# ECG_V1_1.net
KiCad netlist of a schematic drawn in EAGLE
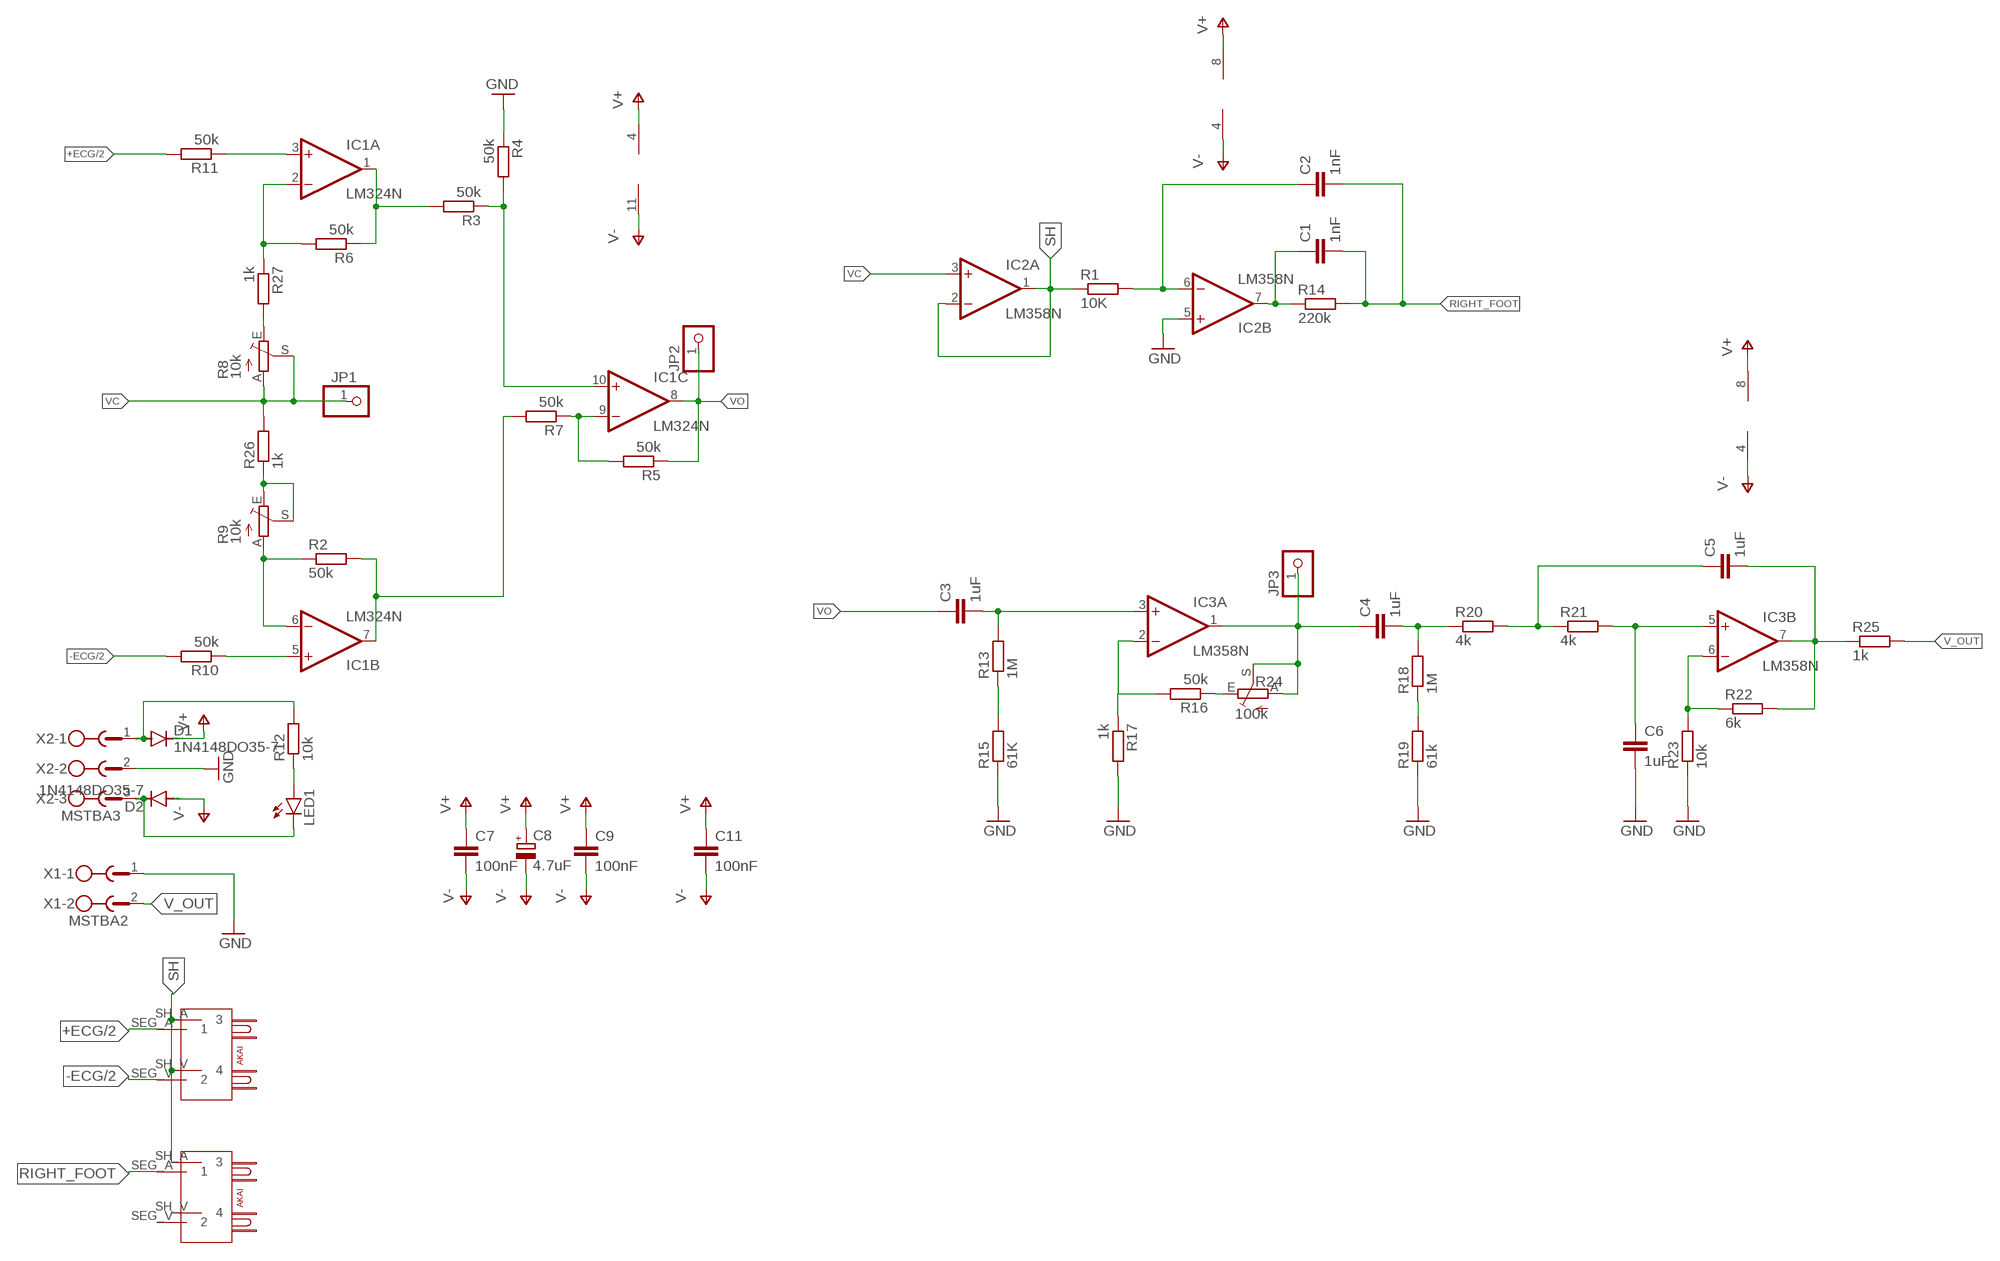
[diagram p0: schematic, sheet 1]

(export (version "E")
  (design (tool "Eeschema 10.0.6"))
  (components
    (comp (ref "C1")
      (value "1nF")
      (footprint "eagle-import:C050-024X044")
      (libsource (lib "eagle-import") (part "C-EU050-024X044"))
    )
    (comp (ref "C2")
      (value "1nF")
      (footprint "eagle-import:C050-024X044")
      (libsource (lib "eagle-import") (part "C-EU050-024X044"))
    )
    (comp (ref "C3")
      (value "1uF")
      (footprint "eagle-import:C075-032X103")
      (libsource (lib "eagle-import") (part "C-EU075-032X103"))
    )
    (comp (ref "C4")
      (value "1uF")
      (footprint "eagle-import:C050-024X044")
      (libsource (lib "eagle-import") (part "C-EU050-024X044"))
    )
    (comp (ref "C5")
      (value "1uF")
      (footprint "eagle-import:C050-024X044")
      (libsource (lib "eagle-import") (part "C-EU050-024X044"))
    )
    (comp (ref "C6")
      (value "1uF")
      (footprint "eagle-import:C050-024X044")
      (libsource (lib "eagle-import") (part "C-EU050-024X044"))
    )
    (comp (ref "C7")
      (value "100nF")
      (footprint "eagle-import:C050-024X044")
      (libsource (lib "eagle-import") (part "C-EU050-024X044"))
    )
    (comp (ref "C8")
      (value "4.7uF")
      (footprint "eagle-import:E2-4")
      (libsource (lib "eagle-import") (part "CPOL-EUE2-4"))
    )
    (comp (ref "C9")
      (value "100nF")
      (footprint "eagle-import:C050-024X044")
      (libsource (lib "eagle-import") (part "C-EU050-024X044"))
    )
    (comp (ref "C11")
      (value "100nF")
      (footprint "eagle-import:C050-024X044")
      (libsource (lib "eagle-import") (part "C-EU050-024X044"))
    )
    (comp (ref "D1")
      (value "1N4148DO35-7")
      (footprint "eagle-import:DO35-7")
      (libsource (lib "eagle-import") (part "1N4148DO35-7"))
    )
    (comp (ref "D2")
      (value "1N4148DO35-7")
      (footprint "eagle-import:DO35-7")
      (libsource (lib "eagle-import") (part "1N4148DO35-7"))
    )
    (comp (ref "IC1")
      (value "LM324N")
      (footprint "eagle-import:DIL14")
      (libsource (lib "eagle-import") (part "LM324N"))
    )
    (comp (ref "IC2")
      (value "LM358N")
      (footprint "eagle-import:DIL08")
      (libsource (lib "eagle-import") (part "LM358N"))
    )
    (comp (ref "IC3")
      (value "LM358N")
      (footprint "eagle-import:DIL08")
      (libsource (lib "eagle-import") (part "LM358N"))
    )
    (comp (ref "JP1")
      (value "PINHD-1X1")
      (footprint "eagle-import:1X01")
      (libsource (lib "eagle-import") (part "PINHD-1X1"))
    )
    (comp (ref "JP2")
      (value "PINHD-1X1")
      (footprint "eagle-import:1X01")
      (libsource (lib "eagle-import") (part "PINHD-1X1"))
    )
    (comp (ref "JP3")
      (value "PINHD-1X1")
      (footprint "eagle-import:1X01")
      (libsource (lib "eagle-import") (part "PINHD-1X1"))
    )
    (comp (ref "LED1")
      (value "LED3MM")
      (footprint "eagle-import:LED3MM")
      (libsource (lib "eagle-import") (part "LED3MM"))
    )
    (comp (ref "R1")
      (value "10K")
      (footprint "eagle-import:0207_7")
      (libsource (lib "eagle-import") (part "R-EU_0207/7"))
    )
    (comp (ref "R2")
      (value "50k")
      (footprint "eagle-import:0207_7")
      (libsource (lib "eagle-import") (part "R-EU_0207/7"))
    )
    (comp (ref "R3")
      (value "50k")
      (footprint "eagle-import:0207_7")
      (libsource (lib "eagle-import") (part "R-EU_0207/7"))
    )
    (comp (ref "R4")
      (value "50k")
      (footprint "eagle-import:0207_7")
      (libsource (lib "eagle-import") (part "R-EU_0207/7"))
    )
    (comp (ref "R5")
      (value "50k")
      (footprint "eagle-import:0207_7")
      (libsource (lib "eagle-import") (part "R-EU_0207/7"))
    )
    (comp (ref "R6")
      (value "50k")
      (footprint "eagle-import:0207_7")
      (libsource (lib "eagle-import") (part "R-EU_0207/7"))
    )
    (comp (ref "R7")
      (value "50k")
      (footprint "eagle-import:0207_7")
      (libsource (lib "eagle-import") (part "R-EU_0207/7"))
    )
    (comp (ref "R8")
      (value "10k")
      (footprint "eagle-import:S64W")
      (libsource (lib "eagle-import") (part "TRIM_EU-S64W"))
    )
    (comp (ref "R9")
      (value "10k")
      (footprint "eagle-import:S64W")
      (libsource (lib "eagle-import") (part "TRIM_EU-S64W"))
    )
    (comp (ref "R10")
      (value "50k")
      (footprint "eagle-import:0207_7")
      (libsource (lib "eagle-import") (part "R-EU_0207/7"))
    )
    (comp (ref "R11")
      (value "50k")
      (footprint "eagle-import:0207_7")
      (libsource (lib "eagle-import") (part "R-EU_0207/7"))
    )
    (comp (ref "R12")
      (value "10k")
      (footprint "eagle-import:0207_7")
      (libsource (lib "eagle-import") (part "R-EU_0207/7"))
    )
    (comp (ref "R13")
      (value "1M")
      (footprint "eagle-import:0207_7")
      (libsource (lib "eagle-import") (part "R-EU_0207/7"))
    )
    (comp (ref "R14")
      (value "220k")
      (footprint "eagle-import:0207_7")
      (libsource (lib "eagle-import") (part "R-EU_0207/7"))
    )
    (comp (ref "R15")
      (value "61K")
      (footprint "eagle-import:0207_7")
      (libsource (lib "eagle-import") (part "R-EU_0207/7"))
    )
    (comp (ref "R16")
      (value "50k")
      (footprint "eagle-import:0207_7")
      (libsource (lib "eagle-import") (part "R-EU_0207/7"))
    )
    (comp (ref "R17")
      (value "1k")
      (footprint "eagle-import:0207_7")
      (libsource (lib "eagle-import") (part "R-EU_0207/7"))
    )
    (comp (ref "R18")
      (value "1M")
      (footprint "eagle-import:0207_7")
      (libsource (lib "eagle-import") (part "R-EU_0207/7"))
    )
    (comp (ref "R19")
      (value "61k")
      (footprint "eagle-import:0207_7")
      (libsource (lib "eagle-import") (part "R-EU_0207/7"))
    )
    (comp (ref "R20")
      (value "4k")
      (footprint "eagle-import:0207_7")
      (libsource (lib "eagle-import") (part "R-EU_0207/7"))
    )
    (comp (ref "R21")
      (value "4k")
      (footprint "eagle-import:0207_7")
      (libsource (lib "eagle-import") (part "R-EU_0207/7"))
    )
    (comp (ref "R22")
      (value "6k")
      (footprint "eagle-import:0207_7")
      (libsource (lib "eagle-import") (part "R-EU_0207/7"))
    )
    (comp (ref "R23")
      (value "10k")
      (footprint "eagle-import:0207_7")
      (libsource (lib "eagle-import") (part "R-EU_0207/7"))
    )
    (comp (ref "R24")
      (value "100k")
      (footprint "eagle-import:S64W")
      (libsource (lib "eagle-import") (part "TRIM_EU-S64W"))
    )
    (comp (ref "R25")
      (value "1k")
      (footprint "eagle-import:0207_7")
      (libsource (lib "eagle-import") (part "R-EU_0207/7"))
    )
    (comp (ref "R26")
      (value "1k")
      (footprint "eagle-import:0207_7")
      (libsource (lib "eagle-import") (part "R-EU_0207/7"))
    )
    (comp (ref "R27")
      (value "1k")
      (footprint "eagle-import:0207_7")
      (libsource (lib "eagle-import") (part "R-EU_0207/7"))
    )
    (comp (ref "U$1")
      (value "AKAI")
      (footprint "eagle-import:DUAL_AKAI")
      (libsource (lib "eagle-import") (part "AKAI"))
    )
    (comp (ref "U$2")
      (value "AKAI")
      (footprint "eagle-import:DUAL_AKAI")
      (libsource (lib "eagle-import") (part "AKAI"))
    )
    (comp (ref "X1")
      (value "MSTBA2")
      (footprint "eagle-import:MSTBA2")
      (fields (field (name "MF") "FARNELL") (field (name "MPN") "1757242"))
      (libsource (lib "eagle-import") (part "MSTBA2"))
    )
    (comp (ref "X2")
      (value "MSTBA3")
      (footprint "eagle-import:MSTBA3")
      (fields (field (name "MF") "FARNELL") (field (name "MPN") "1757255"))
      (libsource (lib "eagle-import") (part "MSTBA3"))
    )
  )
  (nets
    (net (code "1") (name "+ECG{slash}2") (class "Default")
      (node (ref "R11") (pin "2") (pinfunction "2_2") (pintype "passive"))
      (node (ref "U$1") (pin "SEG_A") (pinfunction "1_SEG_A") (pintype "bidirectional"))
    )
    (net (code "2") (name "-ECG{slash}2") (class "Default")
      (node (ref "R10") (pin "2") (pinfunction "2_2") (pintype "passive"))
      (node (ref "U$1") (pin "SEG_V") (pinfunction "2_SEG_V") (pintype "bidirectional"))
    )
    (net (code "3") (name "GND") (class "Default")
      (node (ref "C6") (pin "2") (pinfunction "2_2") (pintype "passive"))
      (node (ref "IC2") (pin "5") (pinfunction "+IN_5") (pintype "input"))
      (node (ref "R15") (pin "1") (pinfunction "1_1") (pintype "passive"))
      (node (ref "R17") (pin "2") (pinfunction "2_2") (pintype "passive"))
      (node (ref "R19") (pin "1") (pinfunction "1_1") (pintype "passive"))
      (node (ref "R23") (pin "1") (pinfunction "1_1") (pintype "passive"))
      (node (ref "R4") (pin "1") (pinfunction "1_1") (pintype "passive"))
      (node (ref "X1") (pin "1") (pinfunction "1_1") (pintype "passive"))
      (node (ref "X2") (pin "2") (pinfunction "1_2") (pintype "passive"))
    )
    (net (code "4") (name "Net-(C4-Pad2)") (class "Default")
      (node (ref "C4") (pin "2") (pinfunction "2_2") (pintype "passive"))
      (node (ref "R18") (pin "2") (pinfunction "2_2") (pintype "passive"))
      (node (ref "R20") (pin "1") (pinfunction "1_1") (pintype "passive"))
    )
    (net (code "5") (name "Net-(C5-Pad1)") (class "Default")
      (node (ref "C5") (pin "1") (pinfunction "1_1") (pintype "passive"))
      (node (ref "R20") (pin "2") (pinfunction "2_2") (pintype "passive"))
      (node (ref "R21") (pin "1") (pinfunction "1_1") (pintype "passive"))
    )
    (net (code "6") (name "Net-(D1-PadA)") (class "Default")
      (node (ref "D1") (pin "A") (pinfunction "A_A") (pintype "passive"))
      (node (ref "R12") (pin "2") (pinfunction "2_2") (pintype "passive"))
      (node (ref "X2") (pin "1") (pinfunction "1_1") (pintype "passive"))
    )
    (net (code "7") (name "Net-(IC1A-+IN)") (class "Default")
      (node (ref "IC1") (pin "3") (pinfunction "+IN_3") (pintype "input"))
      (node (ref "R11") (pin "1") (pinfunction "1_1") (pintype "passive"))
    )
    (net (code "8") (name "Net-(IC1A--IN)") (class "Default")
      (node (ref "IC1") (pin "2") (pinfunction "-IN_2") (pintype "input"))
      (node (ref "R27") (pin "1") (pinfunction "1_1") (pintype "passive"))
      (node (ref "R6") (pin "2") (pinfunction "2_2") (pintype "passive"))
    )
    (net (code "9") (name "Net-(IC1A-OUT)") (class "Default")
      (node (ref "IC1") (pin "1") (pinfunction "OUT_1") (pintype "output"))
      (node (ref "R3") (pin "2") (pinfunction "2_2") (pintype "passive"))
      (node (ref "R6") (pin "1") (pinfunction "1_1") (pintype "passive"))
    )
    (net (code "10") (name "Net-(IC1B-+IN)") (class "Default")
      (node (ref "IC1") (pin "5") (pinfunction "+IN_5") (pintype "input"))
      (node (ref "R10") (pin "1") (pinfunction "1_1") (pintype "passive"))
    )
    (net (code "11") (name "Net-(IC1B--IN)") (class "Default")
      (node (ref "IC1") (pin "6") (pinfunction "-IN_6") (pintype "input"))
      (node (ref "R2") (pin "1") (pinfunction "1_1") (pintype "passive"))
      (node (ref "R9") (pin "A") (pinfunction "A_A") (pintype "passive"))
    )
    (net (code "12") (name "Net-(IC1B-OUT)") (class "Default")
      (node (ref "IC1") (pin "7") (pinfunction "OUT_7") (pintype "output"))
      (node (ref "R2") (pin "2") (pinfunction "2_2") (pintype "passive"))
      (node (ref "R7") (pin "2") (pinfunction "2_2") (pintype "passive"))
    )
    (net (code "13") (name "Net-(IC1C-+IN)") (class "Default")
      (node (ref "IC1") (pin "10") (pinfunction "+IN_10") (pintype "input"))
      (node (ref "R3") (pin "1") (pinfunction "1_1") (pintype "passive"))
      (node (ref "R4") (pin "2") (pinfunction "2_2") (pintype "passive"))
    )
    (net (code "14") (name "Net-(IC1C--IN)") (class "Default")
      (node (ref "IC1") (pin "9") (pinfunction "-IN_9") (pintype "input"))
      (node (ref "R5") (pin "2") (pinfunction "2_2") (pintype "passive"))
      (node (ref "R7") (pin "1") (pinfunction "1_1") (pintype "passive"))
    )
    (net (code "15") (name "Net-(IC2B--IN)") (class "Default")
      (node (ref "C2") (pin "1") (pinfunction "1_1") (pintype "passive"))
      (node (ref "IC2") (pin "6") (pinfunction "-IN_6") (pintype "input"))
      (node (ref "R1") (pin "2") (pinfunction "2_2") (pintype "passive"))
    )
    (net (code "16") (name "Net-(IC2B-OUT)") (class "Default")
      (node (ref "C1") (pin "1") (pinfunction "1_1") (pintype "passive"))
      (node (ref "IC2") (pin "7") (pinfunction "OUT_7") (pintype "output"))
      (node (ref "R14") (pin "1") (pinfunction "1_1") (pintype "passive"))
    )
    (net (code "17") (name "Net-(IC3A-+IN)") (class "Default")
      (node (ref "C3") (pin "2") (pinfunction "2_2") (pintype "passive"))
      (node (ref "IC3") (pin "3") (pinfunction "+IN_3") (pintype "input"))
      (node (ref "R13") (pin "2") (pinfunction "2_2") (pintype "passive"))
    )
    (net (code "18") (name "Net-(IC3A--IN)") (class "Default")
      (node (ref "IC3") (pin "2") (pinfunction "-IN_2") (pintype "input"))
      (node (ref "R16") (pin "2") (pinfunction "2_2") (pintype "passive"))
      (node (ref "R17") (pin "1") (pinfunction "1_1") (pintype "passive"))
    )
    (net (code "19") (name "Net-(IC3A-OUT)") (class "Default")
      (node (ref "C4") (pin "1") (pinfunction "1_1") (pintype "passive"))
      (node (ref "IC3") (pin "1") (pinfunction "OUT_1") (pintype "output"))
      (node (ref "JP3") (pin "1") (pinfunction "1_1") (pintype "passive"))
      (node (ref "R24") (pin "A") (pinfunction "A_A") (pintype "passive"))
      (node (ref "R24") (pin "S") (pinfunction "S_S") (pintype "passive"))
    )
    (net (code "20") (name "Net-(IC3B-+IN)") (class "Default")
      (node (ref "C6") (pin "1") (pinfunction "1_1") (pintype "passive"))
      (node (ref "IC3") (pin "5") (pinfunction "+IN_5") (pintype "input"))
      (node (ref "R21") (pin "2") (pinfunction "2_2") (pintype "passive"))
    )
    (net (code "21") (name "Net-(IC3B--IN)") (class "Default")
      (node (ref "IC3") (pin "6") (pinfunction "-IN_6") (pintype "input"))
      (node (ref "R22") (pin "1") (pinfunction "1_1") (pintype "passive"))
      (node (ref "R23") (pin "2") (pinfunction "2_2") (pintype "passive"))
    )
    (net (code "22") (name "Net-(IC3B-OUT)") (class "Default")
      (node (ref "C5") (pin "2") (pinfunction "2_2") (pintype "passive"))
      (node (ref "IC3") (pin "7") (pinfunction "OUT_7") (pintype "output"))
      (node (ref "R22") (pin "2") (pinfunction "2_2") (pintype "passive"))
      (node (ref "R25") (pin "1") (pinfunction "1_1") (pintype "passive"))
    )
    (net (code "23") (name "Net-(LED1-C)") (class "Default")
      (node (ref "D2") (pin "C") (pinfunction "C_C") (pintype "passive"))
      (node (ref "LED1") (pin "K") (pinfunction "C_K") (pintype "passive"))
      (node (ref "X2") (pin "3") (pinfunction "1_3") (pintype "passive"))
    )
    (net (code "24") (name "Net-(LED1-PadA)") (class "Default")
      (node (ref "LED1") (pin "A") (pinfunction "A_A") (pintype "passive"))
      (node (ref "R12") (pin "1") (pinfunction "1_1") (pintype "passive"))
    )
    (net (code "25") (name "Net-(R13-Pad1)") (class "Default")
      (node (ref "R13") (pin "1") (pinfunction "1_1") (pintype "passive"))
      (node (ref "R15") (pin "2") (pinfunction "2_2") (pintype "passive"))
    )
    (net (code "26") (name "Net-(R16-Pad1)") (class "Default")
      (node (ref "R16") (pin "1") (pinfunction "1_1") (pintype "passive"))
      (node (ref "R24") (pin "E") (pinfunction "E_E") (pintype "passive"))
    )
    (net (code "27") (name "Net-(R18-Pad1)") (class "Default")
      (node (ref "R18") (pin "1") (pinfunction "1_1") (pintype "passive"))
      (node (ref "R19") (pin "2") (pinfunction "2_2") (pintype "passive"))
    )
    (net (code "28") (name "Net-(R26-Pad1)") (class "Default")
      (node (ref "R26") (pin "1") (pinfunction "1_1") (pintype "passive"))
      (node (ref "R9") (pin "E") (pinfunction "E_E") (pintype "passive"))
      (node (ref "R9") (pin "S") (pinfunction "S_S") (pintype "passive"))
    )
    (net (code "29") (name "Net-(R27-Pad2)") (class "Default")
      (node (ref "R27") (pin "2") (pinfunction "2_2") (pintype "passive"))
      (node (ref "R8") (pin "E") (pinfunction "E_E") (pintype "passive"))
    )
    (net (code "30") (name "RIGHT_FOOT") (class "Default")
      (node (ref "C1") (pin "2") (pinfunction "2_2") (pintype "passive"))
      (node (ref "C2") (pin "2") (pinfunction "2_2") (pintype "passive"))
      (node (ref "R14") (pin "2") (pinfunction "2_2") (pintype "passive"))
      (node (ref "U$2") (pin "SEG_A") (pinfunction "1_SEG_A") (pintype "bidirectional"))
    )
    (net (code "31") (name "SH") (class "Default")
      (node (ref "IC2") (pin "1") (pinfunction "OUT_1") (pintype "output"))
      (node (ref "IC2") (pin "2") (pinfunction "-IN_2") (pintype "input"))
      (node (ref "R1") (pin "1") (pinfunction "1_1") (pintype "passive"))
      (node (ref "U$1") (pin "SH_A") (pinfunction "3_SH_A") (pintype "bidirectional"))
      (node (ref "U$1") (pin "SH_V") (pinfunction "4_SH_V") (pintype "bidirectional"))
      (node (ref "U$2") (pin "SH_A") (pinfunction "3_SH_A") (pintype "bidirectional"))
    )
    (net (code "32") (name "V+") (class "Default")
      (node (ref "C11") (pin "1") (pinfunction "1_1") (pintype "passive"))
      (node (ref "C7") (pin "1") (pinfunction "1_1") (pintype "passive"))
      (node (ref "C8") (pin "+") (pinfunction "+_+") (pintype "passive"))
      (node (ref "C9") (pin "1") (pinfunction "1_1") (pintype "passive"))
      (node (ref "D1") (pin "C") (pinfunction "C_C") (pintype "passive"))
      (node (ref "IC1") (pin "4") (pinfunction "V+_4") (pintype "power_in"))
      (node (ref "IC2") (pin "8") (pinfunction "V+_8") (pintype "power_in"))
      (node (ref "IC3") (pin "8") (pinfunction "V+_8") (pintype "power_in"))
    )
    (net (code "33") (name "V-") (class "Default")
      (node (ref "C11") (pin "2") (pinfunction "2_2") (pintype "passive"))
      (node (ref "C7") (pin "2") (pinfunction "2_2") (pintype "passive"))
      (node (ref "C8") (pin "-") (pinfunction "-_-") (pintype "passive"))
      (node (ref "C9") (pin "2") (pinfunction "2_2") (pintype "passive"))
      (node (ref "D2") (pin "A") (pinfunction "A_A") (pintype "passive"))
      (node (ref "IC1") (pin "11") (pinfunction "V-_11") (pintype "power_in"))
      (node (ref "IC2") (pin "4") (pinfunction "V-_4") (pintype "power_in"))
      (node (ref "IC3") (pin "4") (pinfunction "V-_4") (pintype "power_in"))
    )
    (net (code "34") (name "VC") (class "Default")
      (node (ref "IC2") (pin "3") (pinfunction "+IN_3") (pintype "input"))
      (node (ref "JP1") (pin "1") (pinfunction "1_1") (pintype "passive"))
      (node (ref "R26") (pin "2") (pinfunction "2_2") (pintype "passive"))
      (node (ref "R8") (pin "A") (pinfunction "A_A") (pintype "passive"))
      (node (ref "R8") (pin "S") (pinfunction "S_S") (pintype "passive"))
    )
    (net (code "35") (name "VO") (class "Default")
      (node (ref "C3") (pin "1") (pinfunction "1_1") (pintype "passive"))
      (node (ref "IC1") (pin "8") (pinfunction "OUT_8") (pintype "output"))
      (node (ref "JP2") (pin "1") (pinfunction "1_1") (pintype "passive"))
      (node (ref "R5") (pin "1") (pinfunction "1_1") (pintype "passive"))
    )
    (net (code "36") (name "V_OUT") (class "Default")
      (node (ref "R25") (pin "2") (pinfunction "2_2") (pintype "passive"))
      (node (ref "X1") (pin "2") (pinfunction "1_2") (pintype "passive"))
    )
    (net (code "37") (name "unconnected-(U$2-2-PadSEG_V)") (class "Default")
      (node (ref "U$2") (pin "SEG_V") (pinfunction "2_SEG_V") (pintype "bidirectional"))
    )
    (net (code "38") (name "unconnected-(U$2-4-PadSH_V)") (class "Default")
      (node (ref "U$2") (pin "SH_V") (pinfunction "4_SH_V") (pintype "bidirectional"))
    )
  )
)
